# base-2u-psu-adapter.net
KiCad netlist of a schematic drawn in EAGLE
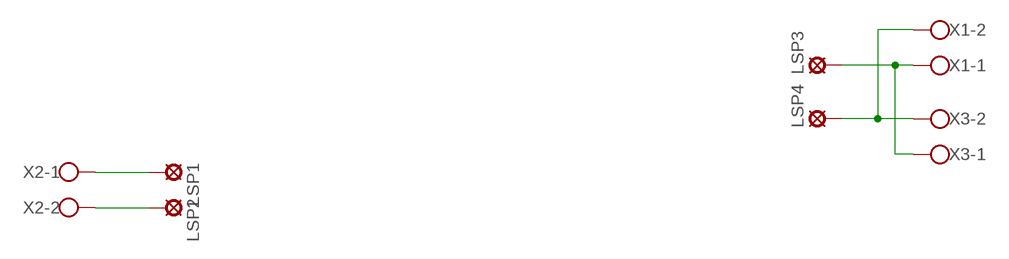
[diagram p0: schematic, sheet 1]

(export (version "E")
  (design (tool "Eeschema 10.0.6"))
  (components
    (comp (ref "LSP1")
      (value "LSP10")
      (footprint "eagle-import:LSP10")
      (libsource (lib "eagle-import") (part "LSP10"))
    )
    (comp (ref "LSP2")
      (value "LSP10")
      (footprint "eagle-import:LSP10")
      (libsource (lib "eagle-import") (part "LSP10"))
    )
    (comp (ref "LSP3")
      (value "LSP10")
      (footprint "eagle-import:LSP10")
      (libsource (lib "eagle-import") (part "LSP10"))
    )
    (comp (ref "LSP4")
      (value "LSP10")
      (footprint "eagle-import:LSP10")
      (libsource (lib "eagle-import") (part "LSP10"))
    )
    (comp (ref "X1")
      (value "W237-102")
      (footprint "eagle-import:W237-102")
      (libsource (lib "eagle-import") (part "W237-102"))
    )
    (comp (ref "X2")
      (value "W237-102")
      (footprint "eagle-import:W237-102")
      (libsource (lib "eagle-import") (part "W237-102"))
    )
    (comp (ref "X3")
      (value "W237-102")
      (footprint "eagle-import:W237-102")
      (libsource (lib "eagle-import") (part "W237-102"))
    )
  )
  (nets
    (net (code "1") (name "Net-(X1A-KL)") (class "Default")
      (node (ref "LSP3") (pin "MP") (pinfunction "MP_MP") (pintype "passive"))
      (node (ref "X1") (pin "1") (pinfunction "KL_1") (pintype "passive"))
      (node (ref "X3") (pin "1") (pinfunction "KL_1") (pintype "passive"))
    )
    (net (code "2") (name "Net-(X1B-KL)") (class "Default")
      (node (ref "LSP4") (pin "MP") (pinfunction "MP_MP") (pintype "passive"))
      (node (ref "X1") (pin "2") (pinfunction "KL_2") (pintype "passive"))
      (node (ref "X3") (pin "2") (pinfunction "KL_2") (pintype "passive"))
    )
    (net (code "3") (name "Net-(X2A-KL)") (class "Default")
      (node (ref "LSP1") (pin "MP") (pinfunction "MP_MP") (pintype "passive"))
      (node (ref "X2") (pin "1") (pinfunction "KL_1") (pintype "passive"))
    )
    (net (code "4") (name "Net-(X2B-KL)") (class "Default")
      (node (ref "LSP2") (pin "MP") (pinfunction "MP_MP") (pintype "passive"))
      (node (ref "X2") (pin "2") (pinfunction "KL_2") (pintype "passive"))
    )
  )
)
